# CSI.net
KiCad netlist of a schematic drawn in Altium Designer
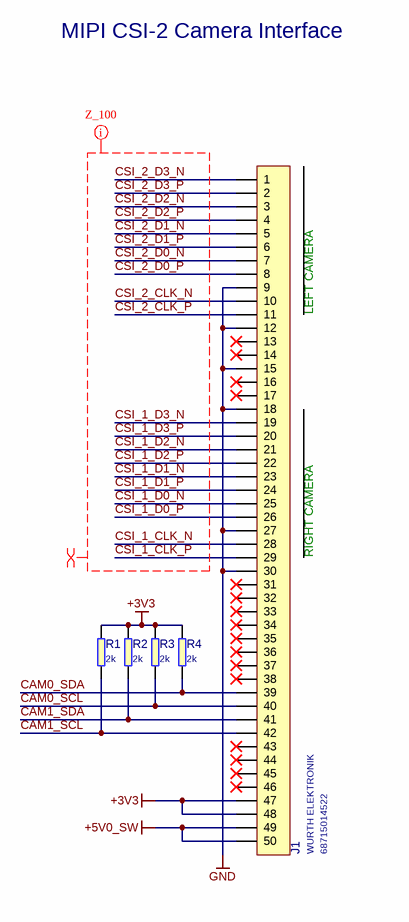
[diagram p0: CSI.SchDoc]

(export (version "E")
  (design (tool "Eeschema 10.0.6"))
  (components
    (comp (ref "J1")
      (value "68715014522")
      (footprint "68715014522")
      (description "0.50mm SMT ZIF Horizontal Bottom Contact WR-FPC")
      (fields (field (name "MANUFACTURER") "WURTH ELEKTRONIK"))
      (libsource (lib "altium-import") (part "root_0_1X50_"))
    )
    (comp (ref "R1")
      (value "2k")
      (footprint "0402")
      (description "SMT Resistor 2k 0402")
      (fields (field (name "PARTNUMBER") "R_2k_0402"))
      (libsource (lib "altium-import") (part "root_3_R_"))
    )
    (comp (ref "R2")
      (value "2k")
      (footprint "0402")
      (description "SMT Resistor 2k 0402")
      (fields (field (name "PARTNUMBER") "R_2k_0402"))
      (libsource (lib "altium-import") (part "root_3_R_"))
    )
    (comp (ref "R3")
      (value "2k")
      (footprint "0402")
      (description "SMT Resistor 2k 0402")
      (fields (field (name "PARTNUMBER") "R_2k_0402"))
      (libsource (lib "altium-import") (part "root_3_R_"))
    )
    (comp (ref "R4")
      (value "2k")
      (footprint "0402")
      (description "SMT Resistor 2k 0402")
      (fields (field (name "PARTNUMBER") "R_2k_0402"))
      (libsource (lib "altium-import") (part "root_3_R_"))
    )
  )
  (nets
    (net (code "1") (name "+3V3") (class "Default")
      (node (ref "J1") (pin "47") (pinfunction "47_47") (pintype "passive"))
      (node (ref "J1") (pin "48") (pinfunction "48_48") (pintype "passive"))
      (node (ref "R1") (pin "1") (pintype "passive"))
      (node (ref "R2") (pin "1") (pintype "passive"))
      (node (ref "R3") (pin "1") (pintype "passive"))
      (node (ref "R4") (pin "1") (pintype "passive"))
    )
    (net (code "2") (name "+5V0_SW") (class "Default")
      (node (ref "J1") (pin "49") (pinfunction "49_49") (pintype "passive"))
      (node (ref "J1") (pin "50") (pinfunction "50_50") (pintype "passive"))
    )
    (net (code "3") (name "/CAM0_SCL") (class "Default")
      (node (ref "J1") (pin "40") (pinfunction "40_40") (pintype "passive"))
      (node (ref "R3") (pin "2") (pintype "passive"))
    )
    (net (code "4") (name "/CAM0_SDA") (class "Default")
      (node (ref "J1") (pin "39") (pinfunction "39_39") (pintype "passive"))
      (node (ref "R4") (pin "2") (pintype "passive"))
    )
    (net (code "5") (name "/CAM1_SCL") (class "Default")
      (node (ref "J1") (pin "42") (pinfunction "42_42") (pintype "passive"))
      (node (ref "R1") (pin "2") (pintype "passive"))
    )
    (net (code "6") (name "/CAM1_SDA") (class "Default")
      (node (ref "J1") (pin "41") (pinfunction "41_41") (pintype "passive"))
      (node (ref "R2") (pin "2") (pintype "passive"))
    )
    (net (code "7") (name "/CSI_1_CLK_N") (class "Default")
      (node (ref "J1") (pin "28") (pinfunction "28_28") (pintype "passive"))
    )
    (net (code "8") (name "/CSI_1_CLK_P") (class "Default")
      (node (ref "J1") (pin "29") (pinfunction "29_29") (pintype "passive"))
    )
    (net (code "9") (name "/CSI_1_D0_N") (class "Default")
      (node (ref "J1") (pin "25") (pinfunction "25_25") (pintype "passive"))
    )
    (net (code "10") (name "/CSI_1_D0_P") (class "Default")
      (node (ref "J1") (pin "26") (pinfunction "26_26") (pintype "passive"))
    )
    (net (code "11") (name "/CSI_1_D1_N") (class "Default")
      (node (ref "J1") (pin "23") (pinfunction "23_23") (pintype "passive"))
    )
    (net (code "12") (name "/CSI_1_D1_P") (class "Default")
      (node (ref "J1") (pin "24") (pinfunction "24_24") (pintype "passive"))
    )
    (net (code "13") (name "/CSI_1_D2_N") (class "Default")
      (node (ref "J1") (pin "21") (pinfunction "21_21") (pintype "passive"))
    )
    (net (code "14") (name "/CSI_1_D2_P") (class "Default")
      (node (ref "J1") (pin "22") (pinfunction "22_22") (pintype "passive"))
    )
    (net (code "15") (name "/CSI_1_D3_N") (class "Default")
      (node (ref "J1") (pin "19") (pinfunction "19_19") (pintype "passive"))
    )
    (net (code "16") (name "/CSI_1_D3_P") (class "Default")
      (node (ref "J1") (pin "20") (pinfunction "20_20") (pintype "passive"))
    )
    (net (code "17") (name "/CSI_2_CLK_N") (class "Default")
      (node (ref "J1") (pin "10") (pinfunction "10_10") (pintype "passive"))
    )
    (net (code "18") (name "/CSI_2_CLK_P") (class "Default")
      (node (ref "J1") (pin "11") (pinfunction "11_11") (pintype "passive"))
    )
    (net (code "19") (name "/CSI_2_D0_N") (class "Default")
      (node (ref "J1") (pin "7") (pinfunction "7_7") (pintype "passive"))
    )
    (net (code "20") (name "/CSI_2_D0_P") (class "Default")
      (node (ref "J1") (pin "8") (pinfunction "8_8") (pintype "passive"))
    )
    (net (code "21") (name "/CSI_2_D1_N") (class "Default")
      (node (ref "J1") (pin "5") (pinfunction "5_5") (pintype "passive"))
    )
    (net (code "22") (name "/CSI_2_D1_P") (class "Default")
      (node (ref "J1") (pin "6") (pinfunction "6_6") (pintype "passive"))
    )
    (net (code "23") (name "/CSI_2_D2_N") (class "Default")
      (node (ref "J1") (pin "3") (pinfunction "3_3") (pintype "passive"))
    )
    (net (code "24") (name "/CSI_2_D2_P") (class "Default")
      (node (ref "J1") (pin "4") (pinfunction "4_4") (pintype "passive"))
    )
    (net (code "25") (name "/CSI_2_D3_N") (class "Default")
      (node (ref "J1") (pin "1") (pinfunction "1_1") (pintype "passive"))
    )
    (net (code "26") (name "/CSI_2_D3_P") (class "Default")
      (node (ref "J1") (pin "2") (pinfunction "2_2") (pintype "passive"))
    )
    (net (code "27") (name "GND") (class "Default")
      (node (ref "J1") (pin "12") (pinfunction "12_12") (pintype "passive"))
      (node (ref "J1") (pin "15") (pinfunction "15_15") (pintype "passive"))
      (node (ref "J1") (pin "18") (pinfunction "18_18") (pintype "passive"))
      (node (ref "J1") (pin "27") (pinfunction "27_27") (pintype "passive"))
      (node (ref "J1") (pin "30") (pinfunction "30_30") (pintype "passive"))
      (node (ref "J1") (pin "9") (pinfunction "9_9") (pintype "passive"))
    )
    (net (code "28") (name "unconnected-(J1-Pad13)") (class "Default")
      (node (ref "J1") (pin "13") (pinfunction "13_13") (pintype "passive+no_connect"))
    )
    (net (code "29") (name "unconnected-(J1-Pad14)") (class "Default")
      (node (ref "J1") (pin "14") (pinfunction "14_14") (pintype "passive+no_connect"))
    )
    (net (code "30") (name "unconnected-(J1-Pad16)") (class "Default")
      (node (ref "J1") (pin "16") (pinfunction "16_16") (pintype "passive+no_connect"))
    )
    (net (code "31") (name "unconnected-(J1-Pad17)") (class "Default")
      (node (ref "J1") (pin "17") (pinfunction "17_17") (pintype "passive+no_connect"))
    )
    (net (code "32") (name "unconnected-(J1-Pad31)") (class "Default")
      (node (ref "J1") (pin "31") (pinfunction "31_31") (pintype "passive+no_connect"))
    )
    (net (code "33") (name "unconnected-(J1-Pad32)") (class "Default")
      (node (ref "J1") (pin "32") (pinfunction "32_32") (pintype "passive+no_connect"))
    )
    (net (code "34") (name "unconnected-(J1-Pad33)") (class "Default")
      (node (ref "J1") (pin "33") (pinfunction "33_33") (pintype "passive+no_connect"))
    )
    (net (code "35") (name "unconnected-(J1-Pad34)") (class "Default")
      (node (ref "J1") (pin "34") (pinfunction "34_34") (pintype "passive+no_connect"))
    )
    (net (code "36") (name "unconnected-(J1-Pad35)") (class "Default")
      (node (ref "J1") (pin "35") (pinfunction "35_35") (pintype "passive+no_connect"))
    )
    (net (code "37") (name "unconnected-(J1-Pad36)") (class "Default")
      (node (ref "J1") (pin "36") (pinfunction "36_36") (pintype "passive+no_connect"))
    )
    (net (code "38") (name "unconnected-(J1-Pad37)") (class "Default")
      (node (ref "J1") (pin "37") (pinfunction "37_37") (pintype "passive+no_connect"))
    )
    (net (code "39") (name "unconnected-(J1-Pad38)") (class "Default")
      (node (ref "J1") (pin "38") (pinfunction "38_38") (pintype "passive+no_connect"))
    )
    (net (code "40") (name "unconnected-(J1-Pad43)") (class "Default")
      (node (ref "J1") (pin "43") (pinfunction "43_43") (pintype "passive+no_connect"))
    )
    (net (code "41") (name "unconnected-(J1-Pad44)") (class "Default")
      (node (ref "J1") (pin "44") (pinfunction "44_44") (pintype "passive+no_connect"))
    )
    (net (code "42") (name "unconnected-(J1-Pad45)") (class "Default")
      (node (ref "J1") (pin "45") (pinfunction "45_45") (pintype "passive+no_connect"))
    )
    (net (code "43") (name "unconnected-(J1-Pad46)") (class "Default")
      (node (ref "J1") (pin "46") (pinfunction "46_46") (pintype "passive+no_connect"))
    )
  )
)
